# rc6551z80_v2.net
KiCad netlist of a schematic drawn in EAGLE
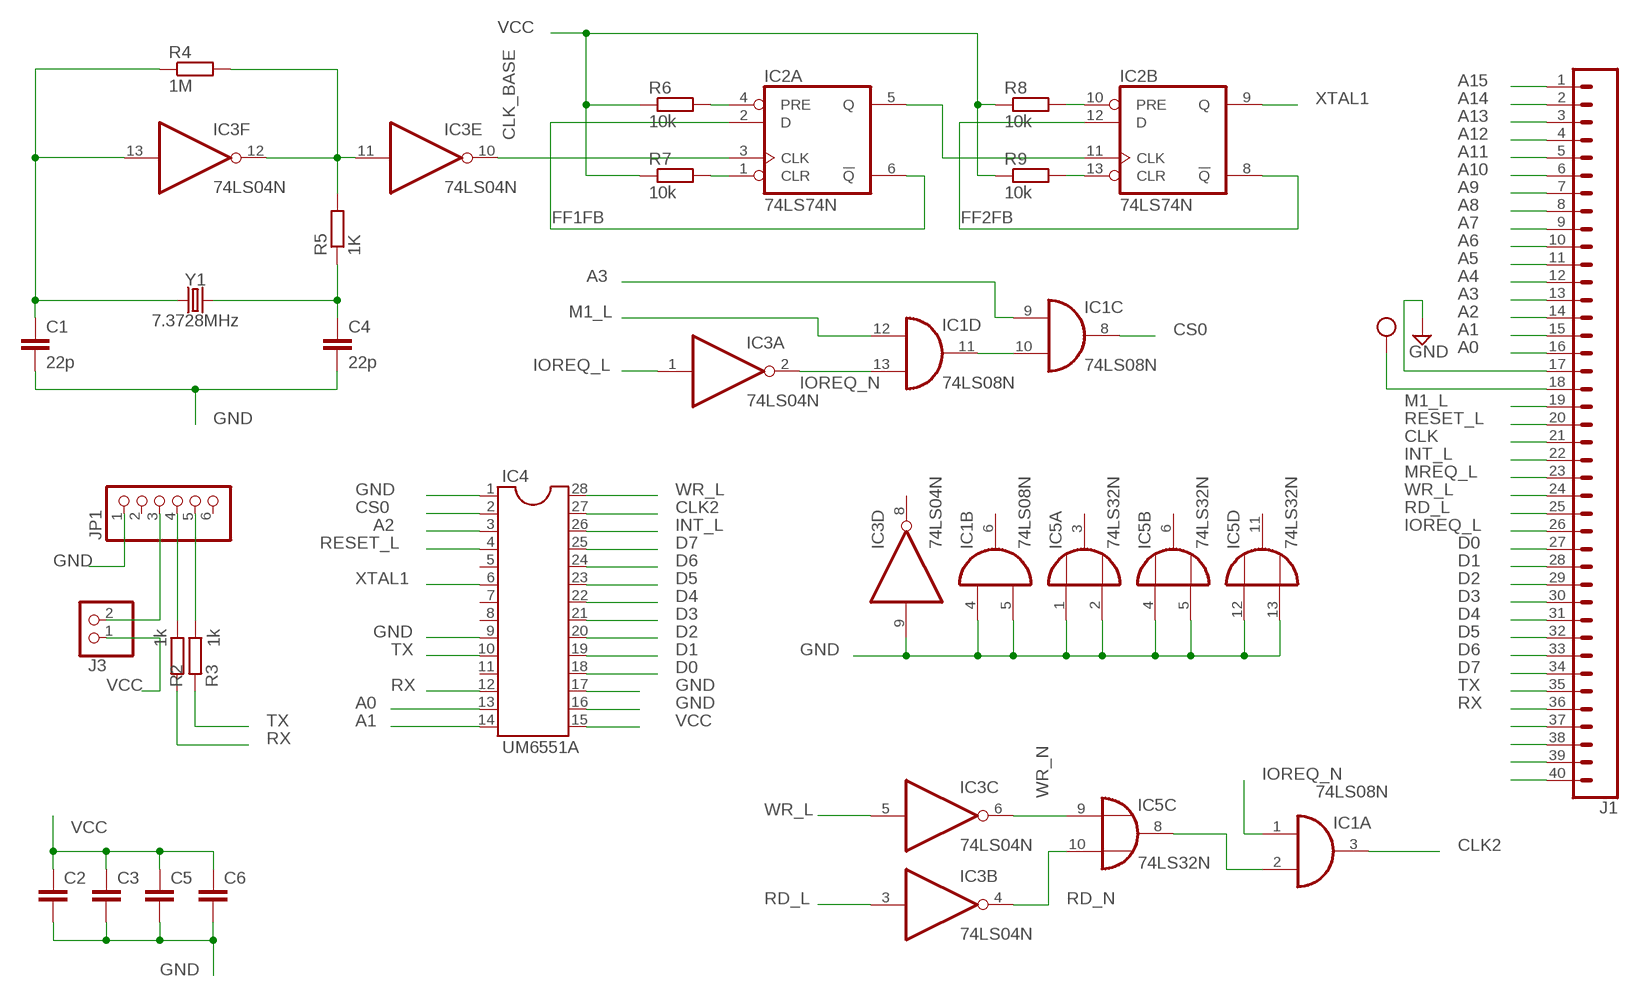
[diagram p0: schematic, sheet 1]

(export (version "E")
  (design (tool "Eeschema 10.0.6"))
  (components
    (comp (ref "C1")
      (value "22p")
      (footprint "eagle-import:C025-024X044")
      (libsource (lib "eagle-import") (part "rcl_334_C-EU025-024X044"))
    )
    (comp (ref "C2")
      (value "C-EU050-025X075")
      (footprint "eagle-import:C050-025X075")
      (libsource (lib "eagle-import") (part "C-EU050-025X075"))
    )
    (comp (ref "C3")
      (value "C-EU050-025X075")
      (footprint "eagle-import:C050-025X075")
      (libsource (lib "eagle-import") (part "C-EU050-025X075"))
    )
    (comp (ref "C4")
      (value "22p")
      (footprint "eagle-import:C025-024X044")
      (libsource (lib "eagle-import") (part "rcl_334_C-EU025-024X044"))
    )
    (comp (ref "C5")
      (value "C-EU050-025X075")
      (footprint "eagle-import:C050-025X075")
      (libsource (lib "eagle-import") (part "C-EU050-025X075"))
    )
    (comp (ref "C6")
      (value "C-EU050-025X075")
      (footprint "eagle-import:C050-025X075")
      (libsource (lib "eagle-import") (part "C-EU050-025X075"))
    )
    (comp (ref "IC1")
      (value "74LS08N")
      (footprint "eagle-import:DIL14")
      (libsource (lib "eagle-import") (part "7408NLS"))
    )
    (comp (ref "IC2")
      (value "74LS74N")
      (footprint "eagle-import:DIL14")
      (libsource (lib "eagle-import") (part "7474NLS"))
    )
    (comp (ref "IC3")
      (value "74LS04N")
      (footprint "eagle-import:DIL14")
      (libsource (lib "eagle-import") (part "7404NLS"))
    )
    (comp (ref "IC4")
      (value "UM6551A")
      (footprint "eagle-import:DIL28-6")
      (libsource (lib "eagle-import") (part "DIL28"))
    )
    (comp (ref "IC5")
      (value "74LS32N")
      (footprint "eagle-import:DIL14")
      (libsource (lib "eagle-import") (part "7432NLS"))
    )
    (comp (ref "J1")
      (value "CONN_40OFFSET")
      (footprint "eagle-import:1X40_OFFSET")
      (libsource (lib "eagle-import") (part "CONN_40OFFSET"))
    )
    (comp (ref "J3")
      (value "PINHD-1X2")
      (footprint "eagle-import:1X02")
      (libsource (lib "eagle-import") (part "PINHD-1X2"))
    )
    (comp (ref "JP1")
      (value "PINHD-1X6")
      (footprint "eagle-import:1X06")
      (libsource (lib "eagle-import") (part "PINHD-1X6"))
    )
    (comp (ref "R2")
      (value "1k")
      (footprint "eagle-import:0204_7")
      (libsource (lib "eagle-import") (part "R-EU_0204/7"))
    )
    (comp (ref "R3")
      (value "1k")
      (footprint "eagle-import:0204_7")
      (libsource (lib "eagle-import") (part "R-EU_0204/7"))
    )
    (comp (ref "R4")
      (value "1M")
      (footprint "eagle-import:0204_7")
      (libsource (lib "eagle-import") (part "R-EU_0204/7"))
    )
    (comp (ref "R5")
      (value "1K")
      (footprint "eagle-import:0204_7")
      (libsource (lib "eagle-import") (part "R-EU_0204/7"))
    )
    (comp (ref "R6")
      (value "10k")
      (footprint "eagle-import:0204_7")
      (libsource (lib "eagle-import") (part "R-EU_0204/7"))
    )
    (comp (ref "R7")
      (value "10k")
      (footprint "eagle-import:0204_7")
      (libsource (lib "eagle-import") (part "R-EU_0204/7"))
    )
    (comp (ref "R8")
      (value "10k")
      (footprint "eagle-import:0204_7")
      (libsource (lib "eagle-import") (part "R-EU_0204/7"))
    )
    (comp (ref "R9")
      (value "10k")
      (footprint "eagle-import:0204_7")
      (libsource (lib "eagle-import") (part "R-EU_0204/7"))
    )
    (comp (ref "Y1")
      (value "7.3728MHz")
      (footprint "eagle-import:HC49U")
      (libsource (lib "eagle-import") (part "CRYSTALPTH-HC49UV"))
    )
  )
  (nets
    (net (code "1") (name "/A0") (class "Default")
      (node (ref "IC4") (pin "13") (pinfunction "13_13") (pintype "passive"))
      (node (ref "J1") (pin "16") (pinfunction "16_16") (pintype "passive"))
    )
    (net (code "2") (name "/A1") (class "Default")
      (node (ref "IC4") (pin "14") (pinfunction "14_14") (pintype "passive"))
      (node (ref "J1") (pin "15") (pinfunction "15_15") (pintype "passive"))
    )
    (net (code "3") (name "/A2") (class "Default")
      (node (ref "IC4") (pin "3") (pinfunction "3_3") (pintype "passive"))
      (node (ref "J1") (pin "14") (pinfunction "14_14") (pintype "passive"))
    )
    (net (code "4") (name "/A3") (class "Default")
      (node (ref "IC1") (pin "9") (pinfunction "I0_9") (pintype "input"))
      (node (ref "J1") (pin "13") (pinfunction "13_13") (pintype "passive"))
    )
    (net (code "5") (name "/A4") (class "Default")
      (node (ref "J1") (pin "12") (pinfunction "12_12") (pintype "passive"))
    )
    (net (code "6") (name "/A5") (class "Default")
      (node (ref "J1") (pin "11") (pinfunction "11_11") (pintype "passive"))
    )
    (net (code "7") (name "/A6") (class "Default")
      (node (ref "J1") (pin "10") (pinfunction "10_10") (pintype "passive"))
    )
    (net (code "8") (name "/A7") (class "Default")
      (node (ref "J1") (pin "9") (pinfunction "9_9") (pintype "passive"))
    )
    (net (code "9") (name "/A8") (class "Default")
      (node (ref "J1") (pin "8") (pinfunction "8_8") (pintype "passive"))
    )
    (net (code "10") (name "/A9") (class "Default")
      (node (ref "J1") (pin "7") (pinfunction "7_7") (pintype "passive"))
    )
    (net (code "11") (name "/A10") (class "Default")
      (node (ref "J1") (pin "6") (pinfunction "6_6") (pintype "passive"))
    )
    (net (code "12") (name "/A11") (class "Default")
      (node (ref "J1") (pin "5") (pinfunction "5_5") (pintype "passive"))
    )
    (net (code "13") (name "/A12") (class "Default")
      (node (ref "J1") (pin "4") (pinfunction "4_4") (pintype "passive"))
    )
    (net (code "14") (name "/A13") (class "Default")
      (node (ref "J1") (pin "3") (pinfunction "3_3") (pintype "passive"))
    )
    (net (code "15") (name "/A14") (class "Default")
      (node (ref "J1") (pin "2") (pinfunction "2_2") (pintype "passive"))
    )
    (net (code "16") (name "/A15") (class "Default")
      (node (ref "J1") (pin "1") (pinfunction "1_1") (pintype "passive"))
    )
    (net (code "17") (name "/CLK") (class "Default")
      (node (ref "J1") (pin "21") (pinfunction "21_21") (pintype "passive"))
    )
    (net (code "18") (name "/CLK2") (class "Default")
      (node (ref "IC1") (pin "3") (pinfunction "O_3") (pintype "output"))
      (node (ref "IC4") (pin "27") (pinfunction "27_27") (pintype "passive"))
    )
    (net (code "19") (name "/CLK_BASE") (class "Default")
      (node (ref "IC2") (pin "3") (pinfunction "CLK_3") (pintype "input"))
      (node (ref "IC3") (pin "10") (pinfunction "O_10") (pintype "output"))
    )
    (net (code "20") (name "/CS0") (class "Default")
      (node (ref "IC1") (pin "8") (pinfunction "O_8") (pintype "output"))
      (node (ref "IC4") (pin "2") (pinfunction "2_2") (pintype "passive"))
    )
    (net (code "21") (name "/D0") (class "Default")
      (node (ref "IC4") (pin "18") (pinfunction "18_18") (pintype "passive"))
      (node (ref "J1") (pin "27") (pinfunction "27_27") (pintype "passive"))
    )
    (net (code "22") (name "/D1") (class "Default")
      (node (ref "IC4") (pin "19") (pinfunction "19_19") (pintype "passive"))
      (node (ref "J1") (pin "28") (pinfunction "28_28") (pintype "passive"))
    )
    (net (code "23") (name "/D2") (class "Default")
      (node (ref "IC4") (pin "20") (pinfunction "20_20") (pintype "passive"))
      (node (ref "J1") (pin "29") (pinfunction "29_29") (pintype "passive"))
    )
    (net (code "24") (name "/D3") (class "Default")
      (node (ref "IC4") (pin "21") (pinfunction "21_21") (pintype "passive"))
      (node (ref "J1") (pin "30") (pinfunction "30_30") (pintype "passive"))
    )
    (net (code "25") (name "/D4") (class "Default")
      (node (ref "IC4") (pin "22") (pinfunction "22_22") (pintype "passive"))
      (node (ref "J1") (pin "31") (pinfunction "31_31") (pintype "passive"))
    )
    (net (code "26") (name "/D5") (class "Default")
      (node (ref "IC4") (pin "23") (pinfunction "23_23") (pintype "passive"))
      (node (ref "J1") (pin "32") (pinfunction "32_32") (pintype "passive"))
    )
    (net (code "27") (name "/D6") (class "Default")
      (node (ref "IC4") (pin "24") (pinfunction "24_24") (pintype "passive"))
      (node (ref "J1") (pin "33") (pinfunction "33_33") (pintype "passive"))
    )
    (net (code "28") (name "/D7") (class "Default")
      (node (ref "IC4") (pin "25") (pinfunction "25_25") (pintype "passive"))
      (node (ref "J1") (pin "34") (pinfunction "34_34") (pintype "passive"))
    )
    (net (code "29") (name "/FF1FB") (class "Default")
      (node (ref "IC2") (pin "2") (pinfunction "D_2") (pintype "input"))
      (node (ref "IC2") (pin "6") (pinfunction "~{Q}_6") (pintype "output"))
    )
    (net (code "30") (name "/FF2FB") (class "Default")
      (node (ref "IC2") (pin "12") (pinfunction "D_12") (pintype "input"))
      (node (ref "IC2") (pin "8") (pinfunction "~{Q}_8") (pintype "output"))
    )
    (net (code "31") (name "/INT_L") (class "Default")
      (node (ref "IC4") (pin "26") (pinfunction "26_26") (pintype "passive"))
      (node (ref "J1") (pin "22") (pinfunction "22_22") (pintype "passive"))
    )
    (net (code "32") (name "/IOREQ_L") (class "Default")
      (node (ref "IC3") (pin "1") (pinfunction "I_1") (pintype "input"))
      (node (ref "J1") (pin "26") (pinfunction "26_26") (pintype "passive"))
    )
    (net (code "33") (name "/IOREQ_N") (class "Default")
      (node (ref "IC1") (pin "1") (pinfunction "I0_1") (pintype "input"))
      (node (ref "IC1") (pin "13") (pinfunction "I1_13") (pintype "input"))
      (node (ref "IC3") (pin "2") (pinfunction "O_2") (pintype "output"))
    )
    (net (code "34") (name "/M1_L") (class "Default")
      (node (ref "IC1") (pin "12") (pinfunction "I0_12") (pintype "input"))
      (node (ref "J1") (pin "19") (pinfunction "19_19") (pintype "passive"))
    )
    (net (code "35") (name "/MREQ_L") (class "Default")
      (node (ref "J1") (pin "23") (pinfunction "23_23") (pintype "passive"))
    )
    (net (code "36") (name "/RD_L") (class "Default")
      (node (ref "IC3") (pin "3") (pinfunction "I_3") (pintype "input"))
      (node (ref "J1") (pin "25") (pinfunction "25_25") (pintype "passive"))
    )
    (net (code "37") (name "/RD_N") (class "Default")
      (node (ref "IC3") (pin "4") (pinfunction "O_4") (pintype "output"))
      (node (ref "IC5") (pin "10") (pinfunction "I1_10") (pintype "input"))
    )
    (net (code "38") (name "/RESET_L") (class "Default")
      (node (ref "IC4") (pin "4") (pinfunction "4_4") (pintype "passive"))
      (node (ref "J1") (pin "20") (pinfunction "20_20") (pintype "passive"))
    )
    (net (code "39") (name "/RX") (class "Default")
      (node (ref "IC4") (pin "12") (pinfunction "12_12") (pintype "passive"))
      (node (ref "J1") (pin "36") (pinfunction "36_36") (pintype "passive"))
      (node (ref "R2") (pin "2") (pinfunction "2_2") (pintype "passive"))
    )
    (net (code "40") (name "/TX") (class "Default")
      (node (ref "IC4") (pin "10") (pinfunction "10_10") (pintype "passive"))
      (node (ref "J1") (pin "35") (pinfunction "35_35") (pintype "passive"))
      (node (ref "R3") (pin "2") (pinfunction "2_2") (pintype "passive"))
    )
    (net (code "41") (name "/WR_L") (class "Default")
      (node (ref "IC3") (pin "5") (pinfunction "I_5") (pintype "input"))
      (node (ref "IC4") (pin "28") (pinfunction "28_28") (pintype "passive"))
      (node (ref "J1") (pin "24") (pinfunction "24_24") (pintype "passive"))
    )
    (net (code "42") (name "/WR_N") (class "Default")
      (node (ref "IC3") (pin "6") (pinfunction "O_6") (pintype "output"))
      (node (ref "IC5") (pin "9") (pinfunction "I0_9") (pintype "input"))
    )
    (net (code "43") (name "/XTAL1") (class "Default")
      (node (ref "IC2") (pin "9") (pinfunction "Q_9") (pintype "output"))
      (node (ref "IC4") (pin "6") (pinfunction "6_6") (pintype "passive"))
    )
    (net (code "44") (name "GND") (class "Default")
      (node (ref "C1") (pin "2") (pinfunction "2_2") (pintype "passive"))
      (node (ref "C2") (pin "2") (pinfunction "2_2") (pintype "passive"))
      (node (ref "C3") (pin "2") (pinfunction "2_2") (pintype "passive"))
      (node (ref "C4") (pin "2") (pinfunction "2_2") (pintype "passive"))
      (node (ref "C5") (pin "2") (pinfunction "2_2") (pintype "passive"))
      (node (ref "C6") (pin "2") (pinfunction "2_2") (pintype "passive"))
      (node (ref "IC1") (pin "4") (pinfunction "I0_4") (pintype "input"))
      (node (ref "IC1") (pin "5") (pinfunction "I1_5") (pintype "input"))
      (node (ref "IC3") (pin "9") (pinfunction "I_9") (pintype "input"))
      (node (ref "IC4") (pin "1") (pinfunction "1_1") (pintype "passive"))
      (node (ref "IC4") (pin "16") (pinfunction "16_16") (pintype "passive"))
      (node (ref "IC4") (pin "17") (pinfunction "17_17") (pintype "passive"))
      (node (ref "IC4") (pin "9") (pinfunction "9_9") (pintype "passive"))
      (node (ref "IC5") (pin "1") (pinfunction "I0_1") (pintype "input"))
      (node (ref "IC5") (pin "12") (pinfunction "I0_12") (pintype "input"))
      (node (ref "IC5") (pin "13") (pinfunction "I1_13") (pintype "input"))
      (node (ref "IC5") (pin "2") (pinfunction "I1_2") (pintype "input"))
      (node (ref "IC5") (pin "4") (pinfunction "I0_4") (pintype "input"))
      (node (ref "IC5") (pin "5") (pinfunction "I1_5") (pintype "input"))
      (node (ref "J1") (pin "17") (pinfunction "17_17") (pintype "passive"))
      (node (ref "JP1") (pin "1") (pinfunction "1_1") (pintype "passive"))
    )
    (net (code "45") (name "Net-(C4-Pad1)") (class "Default")
      (node (ref "C4") (pin "1") (pinfunction "1_1") (pintype "passive"))
      (node (ref "R5") (pin "1") (pinfunction "1_1") (pintype "passive"))
      (node (ref "Y1") (pin "2") (pinfunction "2_2") (pintype "passive"))
    )
    (net (code "46") (name "Net-(IC1A-I1)") (class "Default")
      (node (ref "IC1") (pin "2") (pinfunction "I1_2") (pintype "input"))
      (node (ref "IC5") (pin "8") (pinfunction "O_8") (pintype "output"))
    )
    (net (code "47") (name "Net-(IC1C-I1)") (class "Default")
      (node (ref "IC1") (pin "10") (pinfunction "I1_10") (pintype "input"))
      (node (ref "IC1") (pin "11") (pinfunction "O_11") (pintype "output"))
    )
    (net (code "48") (name "Net-(IC2A-CLR)") (class "Default")
      (node (ref "IC2") (pin "1") (pinfunction "CLR_1") (pintype "input"))
      (node (ref "R7") (pin "2") (pinfunction "2_2") (pintype "passive"))
    )
    (net (code "49") (name "Net-(IC2A-PRE)") (class "Default")
      (node (ref "IC2") (pin "4") (pinfunction "PRE_4") (pintype "input"))
      (node (ref "R6") (pin "2") (pinfunction "2_2") (pintype "passive"))
    )
    (net (code "50") (name "Net-(IC2A-Q)") (class "Default")
      (node (ref "IC2") (pin "11") (pinfunction "CLK_11") (pintype "input"))
      (node (ref "IC2") (pin "5") (pinfunction "Q_5") (pintype "output"))
    )
    (net (code "51") (name "Net-(IC2B-CLR)") (class "Default")
      (node (ref "IC2") (pin "13") (pinfunction "CLR_13") (pintype "input"))
      (node (ref "R9") (pin "2") (pinfunction "2_2") (pintype "passive"))
    )
    (net (code "52") (name "Net-(IC2B-PRE)") (class "Default")
      (node (ref "IC2") (pin "10") (pinfunction "PRE_10") (pintype "input"))
      (node (ref "R8") (pin "2") (pinfunction "2_2") (pintype "passive"))
    )
    (net (code "53") (name "Net-(IC3E-I)") (class "Default")
      (node (ref "IC3") (pin "11") (pinfunction "I_11") (pintype "input"))
      (node (ref "IC3") (pin "12") (pinfunction "O_12") (pintype "output"))
      (node (ref "R4") (pin "2") (pinfunction "2_2") (pintype "passive"))
      (node (ref "R5") (pin "2") (pinfunction "2_2") (pintype "passive"))
    )
    (net (code "54") (name "Net-(IC3F-I)") (class "Default")
      (node (ref "C1") (pin "1") (pinfunction "1_1") (pintype "passive"))
      (node (ref "IC3") (pin "13") (pinfunction "I_13") (pintype "input"))
      (node (ref "R4") (pin "1") (pinfunction "1_1") (pintype "passive"))
      (node (ref "Y1") (pin "1") (pinfunction "1_1") (pintype "passive"))
    )
    (net (code "55") (name "Net-(J3-Pad2)") (class "Default")
      (node (ref "J3") (pin "2") (pinfunction "2_2") (pintype "passive"))
      (node (ref "JP1") (pin "3") (pinfunction "3_3") (pintype "passive"))
    )
    (net (code "56") (name "Net-(JP1-Pad4)") (class "Default")
      (node (ref "JP1") (pin "4") (pinfunction "4_4") (pintype "passive"))
      (node (ref "R2") (pin "1") (pinfunction "1_1") (pintype "passive"))
    )
    (net (code "57") (name "Net-(JP1-Pad5)") (class "Default")
      (node (ref "JP1") (pin "5") (pinfunction "5_5") (pintype "passive"))
      (node (ref "R3") (pin "1") (pinfunction "1_1") (pintype "passive"))
    )
    (net (code "58") (name "VCC") (class "Default")
      (node (ref "C2") (pin "1") (pinfunction "1_1") (pintype "passive"))
      (node (ref "C3") (pin "1") (pinfunction "1_1") (pintype "passive"))
      (node (ref "C5") (pin "1") (pinfunction "1_1") (pintype "passive"))
      (node (ref "C6") (pin "1") (pinfunction "1_1") (pintype "passive"))
      (node (ref "IC4") (pin "15") (pinfunction "15_15") (pintype "passive"))
      (node (ref "J1") (pin "18") (pinfunction "18_18") (pintype "passive"))
      (node (ref "J3") (pin "1") (pinfunction "1_1") (pintype "passive"))
      (node (ref "R6") (pin "1") (pinfunction "1_1") (pintype "passive"))
      (node (ref "R7") (pin "1") (pinfunction "1_1") (pintype "passive"))
      (node (ref "R8") (pin "1") (pinfunction "1_1") (pintype "passive"))
      (node (ref "R9") (pin "1") (pinfunction "1_1") (pintype "passive"))
    )
    (net (code "59") (name "unconnected-(IC1B-O-Pad6)") (class "Default")
      (node (ref "IC1") (pin "6") (pinfunction "O_6") (pintype "output"))
    )
    (net (code "60") (name "unconnected-(IC3D-O-Pad8)") (class "Default")
      (node (ref "IC3") (pin "8") (pinfunction "O_8") (pintype "output"))
    )
    (net (code "61") (name "unconnected-(IC4-Pad5)") (class "Default")
      (node (ref "IC4") (pin "5") (pinfunction "5_5") (pintype "passive"))
    )
    (net (code "62") (name "unconnected-(IC4-Pad7)") (class "Default")
      (node (ref "IC4") (pin "7") (pinfunction "7_7") (pintype "passive"))
    )
    (net (code "63") (name "unconnected-(IC4-Pad8)") (class "Default")
      (node (ref "IC4") (pin "8") (pinfunction "8_8") (pintype "passive"))
    )
    (net (code "64") (name "unconnected-(IC4-Pad11)") (class "Default")
      (node (ref "IC4") (pin "11") (pinfunction "11_11") (pintype "passive"))
    )
    (net (code "65") (name "unconnected-(IC5A-O-Pad3)") (class "Default")
      (node (ref "IC5") (pin "3") (pinfunction "O_3") (pintype "output"))
    )
    (net (code "66") (name "unconnected-(IC5B-O-Pad6)") (class "Default")
      (node (ref "IC5") (pin "6") (pinfunction "O_6") (pintype "output"))
    )
    (net (code "67") (name "unconnected-(IC5D-O-Pad11)") (class "Default")
      (node (ref "IC5") (pin "11") (pinfunction "O_11") (pintype "output"))
    )
    (net (code "68") (name "unconnected-(J1-Pad37)") (class "Default")
      (node (ref "J1") (pin "37") (pinfunction "37_37") (pintype "passive"))
    )
    (net (code "69") (name "unconnected-(J1-Pad38)") (class "Default")
      (node (ref "J1") (pin "38") (pinfunction "38_38") (pintype "passive"))
    )
    (net (code "70") (name "unconnected-(J1-Pad39)") (class "Default")
      (node (ref "J1") (pin "39") (pinfunction "39_39") (pintype "passive"))
    )
    (net (code "71") (name "unconnected-(J1-Pad40)") (class "Default")
      (node (ref "J1") (pin "40") (pinfunction "40_40") (pintype "passive"))
    )
    (net (code "72") (name "unconnected-(JP1-Pad2)") (class "Default")
      (node (ref "JP1") (pin "2") (pinfunction "2_2") (pintype "passive"))
    )
    (net (code "73") (name "unconnected-(JP1-Pad6)") (class "Default")
      (node (ref "JP1") (pin "6") (pinfunction "6_6") (pintype "passive"))
    )
  )
)
